# XbeeFeatherWing.net
KiCad netlist of a schematic drawn in EAGLE
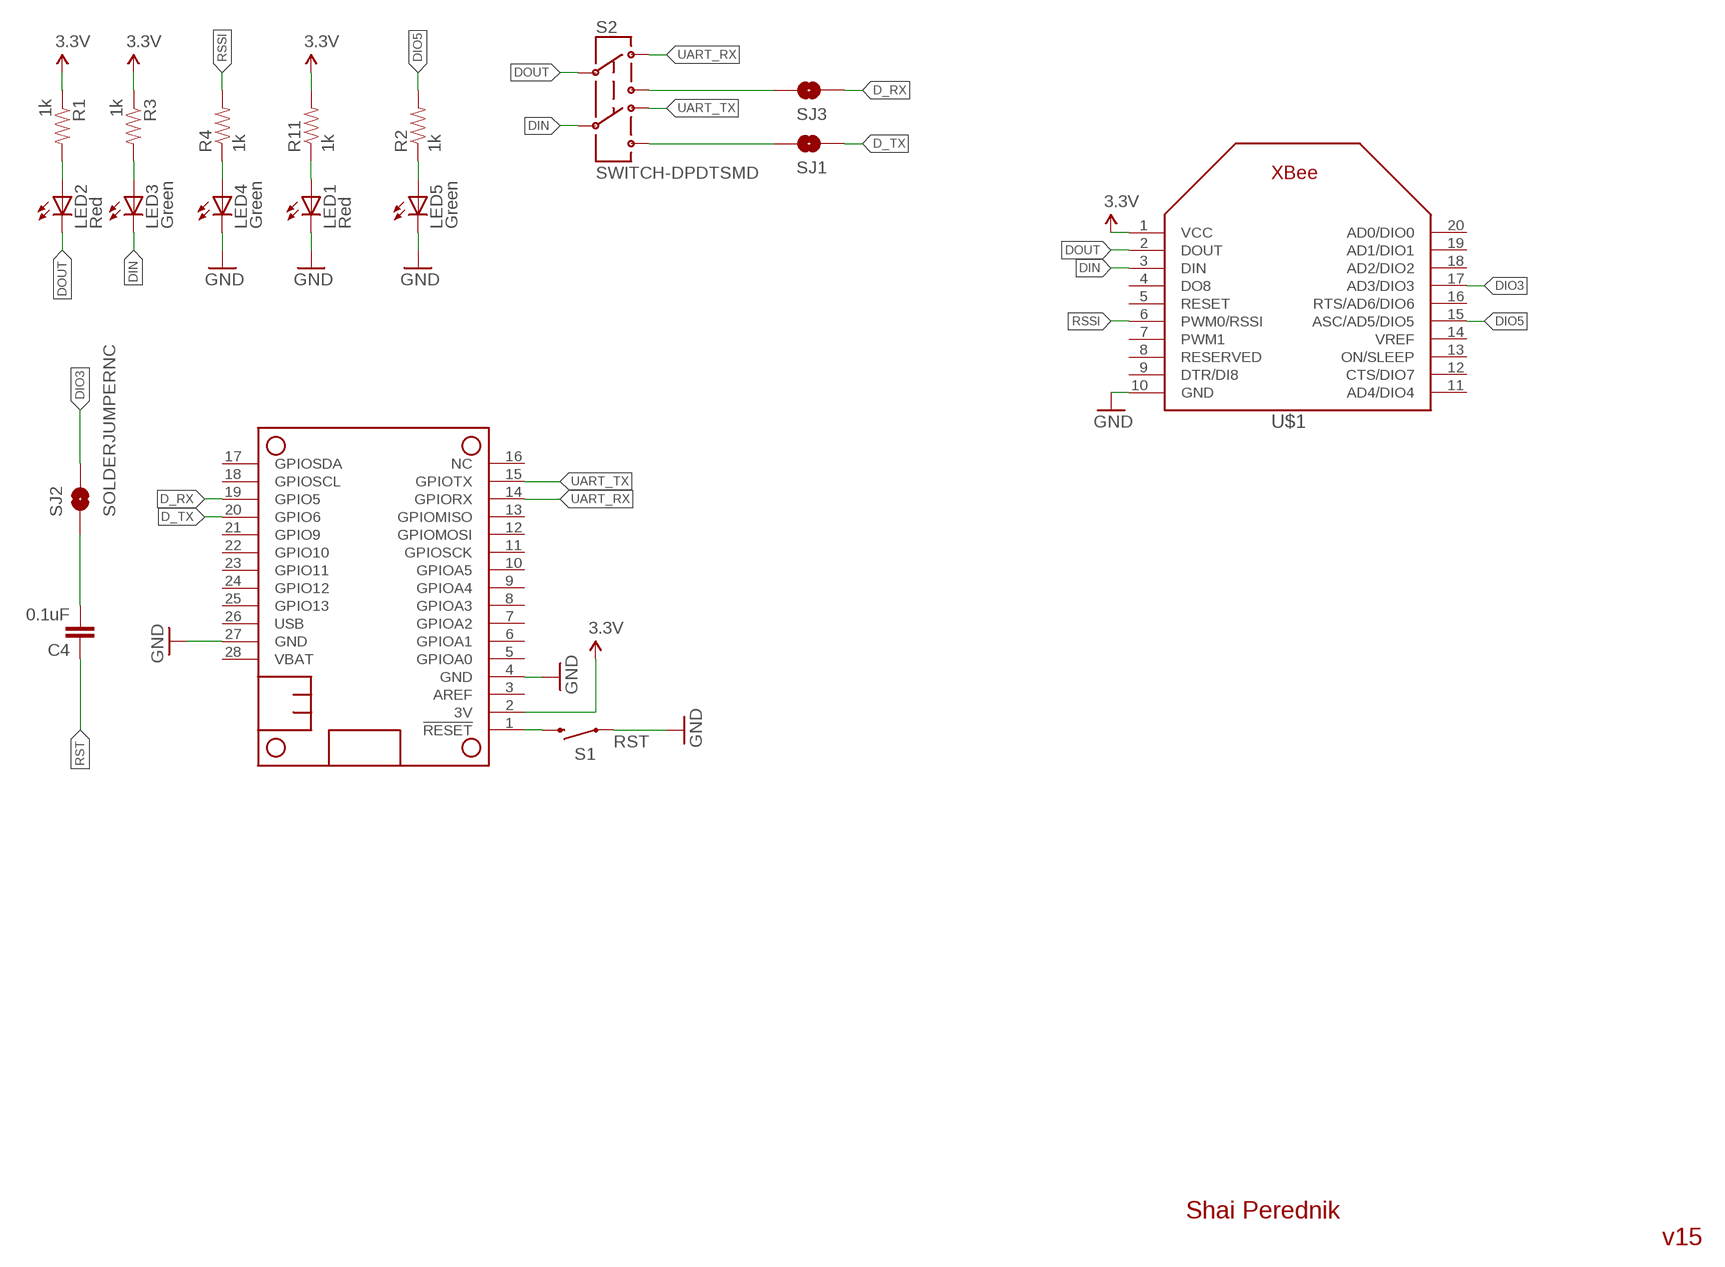
[diagram p0: schematic, sheet 1]

(export (version "E")
  (design (tool "Eeschema 10.0.6"))
  (components
    (comp (ref "C4")
      (value "0.1uF")
      (footprint "eagle-import:0603-CAP")
      (libsource (lib "eagle-import") (part "0.1UF-25V(+80/-20%)(0603)"))
    )
    (comp (ref "LED1")
      (value "Red")
      (footprint "eagle-import:LED-0603")
      (libsource (lib "eagle-import") (part "LED-RED0603"))
    )
    (comp (ref "LED2")
      (value "Red")
      (footprint "eagle-import:LED-0603")
      (libsource (lib "eagle-import") (part "LED-RED0603"))
    )
    (comp (ref "LED3")
      (value "Green")
      (footprint "eagle-import:LED-0603")
      (libsource (lib "eagle-import") (part "LED-GREEN0603"))
    )
    (comp (ref "LED4")
      (value "Green")
      (footprint "eagle-import:LED-0603")
      (libsource (lib "eagle-import") (part "LED-GREEN0603"))
    )
    (comp (ref "LED5")
      (value "Green")
      (footprint "eagle-import:LED-0603")
      (libsource (lib "eagle-import") (part "LED-GREEN0603"))
    )
    (comp (ref "MS2")
      (value "MICROSHIELD_NODIM")
      (footprint "eagle-import:MICROSHIELD_DIM")
      (libsource (lib "eagle-import") (part "MICROSHIELD_NODIM"))
    )
    (comp (ref "R1")
      (value "1k")
      (footprint "eagle-import:0603-RES")
      (libsource (lib "eagle-import") (part "1KOHM1/10W1%(0603)"))
    )
    (comp (ref "R2")
      (value "1k")
      (footprint "eagle-import:0603-RES")
      (libsource (lib "eagle-import") (part "1KOHM1/10W1%(0603)"))
    )
    (comp (ref "R3")
      (value "1k")
      (footprint "eagle-import:0603-RES")
      (libsource (lib "eagle-import") (part "1KOHM1/10W1%(0603)"))
    )
    (comp (ref "R4")
      (value "1k")
      (footprint "eagle-import:0603-RES")
      (libsource (lib "eagle-import") (part "1KOHM1/10W1%(0603)"))
    )
    (comp (ref "R11")
      (value "1k")
      (footprint "eagle-import:0603-RES")
      (libsource (lib "eagle-import") (part "1KOHM1/10W1%(0603)"))
    )
    (comp (ref "S1")
      (value "SWITCH-MOMENTARY-2SMD")
      (footprint "eagle-import:TACTILE_SWITCH_SMD")
      (libsource (lib "eagle-import") (part "SWITCH-MOMENTARY-2SMD"))
    )
    (comp (ref "S2")
      (value "SWITCH-DPDTSMD")
      (footprint "eagle-import:AYZ0202")
      (libsource (lib "eagle-import") (part "SWITCH-DPDTSMD"))
    )
    (comp (ref "SJ1")
      (value "D_TX")
      (footprint "eagle-import:SJ_2S")
      (libsource (lib "eagle-import") (part "SOLDERJUMPERNC"))
    )
    (comp (ref "SJ2")
      (value "SOLDERJUMPERNC")
      (footprint "eagle-import:SJ_2S")
      (libsource (lib "eagle-import") (part "SparkFun-Retired_SOLDERJUMPERNC"))
    )
    (comp (ref "SJ3")
      (value "D_RX")
      (footprint "eagle-import:SJ_2S")
      (libsource (lib "eagle-import") (part "SOLDERJUMPERNC"))
    )
    (comp (ref "U$1")
      (value "XBEE")
      (footprint "eagle-import:XBEE")
      (libsource (lib "eagle-import") (part "XBEE"))
    )
  )
  (nets
    (net (code "1") (name "/USB") (class "Default")
      (node (ref "MS2") (pin "26") (pinfunction "USB_26") (pintype "power_in"))
    )
    (net (code "2") (name "/VBAT") (class "Default")
      (node (ref "MS2") (pin "28") (pinfunction "VBAT_28") (pintype "power_in"))
    )
    (net (code "3") (name "3.3V") (class "Default")
      (node (ref "MS2") (pin "2") (pinfunction "3V_2") (pintype "power_in"))
      (node (ref "R1") (pin "1") (pinfunction "1_1") (pintype "passive"))
      (node (ref "R11") (pin "2") (pinfunction "2_2") (pintype "passive"))
      (node (ref "R3") (pin "1") (pinfunction "1_1") (pintype "passive"))
      (node (ref "U$1") (pin "1") (pinfunction "VCC_1") (pintype "power_in"))
    )
    (net (code "4") (name "DIN") (class "Default")
      (node (ref "LED3") (pin "C") (pinfunction "C_C") (pintype "passive"))
      (node (ref "S2") (pin "5") (pinfunction "5_5") (pintype "bidirectional"))
      (node (ref "U$1") (pin "3") (pinfunction "DIN_3") (pintype "input"))
    )
    (net (code "5") (name "DIO3") (class "Default")
      (node (ref "SJ2") (pin "2") (pinfunction "2_2") (pintype "passive"))
      (node (ref "U$1") (pin "17") (pinfunction "AD3/DIO3_17") (pintype "bidirectional"))
    )
    (net (code "6") (name "DIO5") (class "Default")
      (node (ref "R2") (pin "2") (pinfunction "2_2") (pintype "passive"))
      (node (ref "U$1") (pin "15") (pinfunction "ASC/AD5/DIO5_15") (pintype "bidirectional"))
    )
    (net (code "7") (name "DOUT") (class "Default")
      (node (ref "LED2") (pin "C") (pinfunction "C_C") (pintype "passive"))
      (node (ref "S2") (pin "2") (pinfunction "2_2") (pintype "bidirectional"))
      (node (ref "U$1") (pin "2") (pinfunction "DOUT_2") (pintype "output"))
    )
    (net (code "8") (name "D_RX") (class "Default")
      (node (ref "MS2") (pin "19") (pinfunction "GPIO5_19") (pintype "bidirectional"))
      (node (ref "SJ3") (pin "1") (pinfunction "1_1") (pintype "passive"))
    )
    (net (code "9") (name "D_TX") (class "Default")
      (node (ref "MS2") (pin "20") (pinfunction "GPIO6_20") (pintype "bidirectional"))
      (node (ref "SJ1") (pin "1") (pinfunction "1_1") (pintype "passive"))
    )
    (net (code "10") (name "GND") (class "Default")
      (node (ref "LED1") (pin "C") (pinfunction "C_C") (pintype "passive"))
      (node (ref "LED4") (pin "C") (pinfunction "C_C") (pintype "passive"))
      (node (ref "LED5") (pin "C") (pinfunction "C_C") (pintype "passive"))
      (node (ref "MS2") (pin "27") (pinfunction "GND_27") (pintype "power_in"))
      (node (ref "MS2") (pin "4") (pinfunction "GND_4") (pintype "power_in"))
      (node (ref "S1") (pin "1") (pinfunction "1_1") (pintype "passive"))
      (node (ref "U$1") (pin "10") (pinfunction "GND_10") (pintype "power_in"))
    )
    (net (code "11") (name "Net-(C4-Pad2)") (class "Default")
      (node (ref "C4") (pin "2") (pinfunction "2_2") (pintype "passive"))
      (node (ref "SJ2") (pin "1") (pinfunction "1_1") (pintype "passive"))
    )
    (net (code "12") (name "Net-(LED1-PadA)") (class "Default")
      (node (ref "LED1") (pin "A") (pinfunction "A_A") (pintype "passive"))
      (node (ref "R11") (pin "1") (pinfunction "1_1") (pintype "passive"))
    )
    (net (code "13") (name "Net-(LED2-PadA)") (class "Default")
      (node (ref "LED2") (pin "A") (pinfunction "A_A") (pintype "passive"))
      (node (ref "R1") (pin "2") (pinfunction "2_2") (pintype "passive"))
    )
    (net (code "14") (name "Net-(LED3-PadA)") (class "Default")
      (node (ref "LED3") (pin "A") (pinfunction "A_A") (pintype "passive"))
      (node (ref "R3") (pin "2") (pinfunction "2_2") (pintype "passive"))
    )
    (net (code "15") (name "Net-(LED4-PadA)") (class "Default")
      (node (ref "LED4") (pin "A") (pinfunction "A_A") (pintype "passive"))
      (node (ref "R4") (pin "1") (pinfunction "1_1") (pintype "passive"))
    )
    (net (code "16") (name "Net-(LED5-PadA)") (class "Default")
      (node (ref "LED5") (pin "A") (pinfunction "A_A") (pintype "passive"))
      (node (ref "R2") (pin "1") (pinfunction "1_1") (pintype "passive"))
    )
    (net (code "17") (name "Net-(S2-Pad3)") (class "Default")
      (node (ref "S2") (pin "3") (pinfunction "3_3") (pintype "bidirectional"))
      (node (ref "SJ3") (pin "2") (pinfunction "2_2") (pintype "passive"))
    )
    (net (code "18") (name "Net-(S2-Pad6)") (class "Default")
      (node (ref "S2") (pin "6") (pinfunction "6_6") (pintype "bidirectional"))
      (node (ref "SJ1") (pin "2") (pinfunction "2_2") (pintype "passive"))
    )
    (net (code "19") (name "RSSI") (class "Default")
      (node (ref "R4") (pin "2") (pinfunction "2_2") (pintype "passive"))
      (node (ref "U$1") (pin "6") (pinfunction "PWM0/RSSI_6") (pintype "output"))
    )
    (net (code "20") (name "RST") (class "Default")
      (node (ref "C4") (pin "1") (pinfunction "1_1") (pintype "passive"))
      (node (ref "MS2") (pin "1") (pinfunction "~{RESET}_1") (pintype "input"))
      (node (ref "S1") (pin "3") (pinfunction "2_3") (pintype "passive"))
    )
    (net (code "21") (name "UART_RX") (class "Default")
      (node (ref "MS2") (pin "14") (pinfunction "GPIORX_14") (pintype "bidirectional"))
      (node (ref "S2") (pin "1") (pinfunction "1_1") (pintype "bidirectional"))
    )
    (net (code "22") (name "UART_TX") (class "Default")
      (node (ref "MS2") (pin "15") (pinfunction "GPIOTX_15") (pintype "bidirectional"))
      (node (ref "S2") (pin "4") (pinfunction "4_4") (pintype "bidirectional"))
    )
    (net (code "23") (name "unconnected-(MS2-AREF-Pad3)") (class "Default")
      (node (ref "MS2") (pin "3") (pinfunction "AREF_3") (pintype "passive"))
    )
    (net (code "24") (name "unconnected-(MS2-GPIO9-Pad21)") (class "Default")
      (node (ref "MS2") (pin "21") (pinfunction "GPIO9_21") (pintype "bidirectional"))
    )
    (net (code "25") (name "unconnected-(MS2-GPIO10-Pad22)") (class "Default")
      (node (ref "MS2") (pin "22") (pinfunction "GPIO10_22") (pintype "bidirectional"))
    )
    (net (code "26") (name "unconnected-(MS2-GPIO11-Pad23)") (class "Default")
      (node (ref "MS2") (pin "23") (pinfunction "GPIO11_23") (pintype "bidirectional"))
    )
    (net (code "27") (name "unconnected-(MS2-GPIO12-Pad24)") (class "Default")
      (node (ref "MS2") (pin "24") (pinfunction "GPIO12_24") (pintype "bidirectional"))
    )
    (net (code "28") (name "unconnected-(MS2-GPIO13-Pad25)") (class "Default")
      (node (ref "MS2") (pin "25") (pinfunction "GPIO13_25") (pintype "bidirectional"))
    )
    (net (code "29") (name "unconnected-(MS2-GPIOA0-Pad5)") (class "Default")
      (node (ref "MS2") (pin "5") (pinfunction "GPIOA0_5") (pintype "bidirectional"))
    )
    (net (code "30") (name "unconnected-(MS2-GPIOA1-Pad6)") (class "Default")
      (node (ref "MS2") (pin "6") (pinfunction "GPIOA1_6") (pintype "bidirectional"))
    )
    (net (code "31") (name "unconnected-(MS2-GPIOA2-Pad7)") (class "Default")
      (node (ref "MS2") (pin "7") (pinfunction "GPIOA2_7") (pintype "bidirectional"))
    )
    (net (code "32") (name "unconnected-(MS2-GPIOA3-Pad8)") (class "Default")
      (node (ref "MS2") (pin "8") (pinfunction "GPIOA3_8") (pintype "bidirectional"))
    )
    (net (code "33") (name "unconnected-(MS2-GPIOA4-Pad9)") (class "Default")
      (node (ref "MS2") (pin "9") (pinfunction "GPIOA4_9") (pintype "bidirectional"))
    )
    (net (code "34") (name "unconnected-(MS2-GPIOA5-Pad10)") (class "Default")
      (node (ref "MS2") (pin "10") (pinfunction "GPIOA5_10") (pintype "bidirectional"))
    )
    (net (code "35") (name "unconnected-(MS2-GPIOMISO-Pad13)") (class "Default")
      (node (ref "MS2") (pin "13") (pinfunction "GPIOMISO_13") (pintype "bidirectional"))
    )
    (net (code "36") (name "unconnected-(MS2-GPIOMOSI-Pad12)") (class "Default")
      (node (ref "MS2") (pin "12") (pinfunction "GPIOMOSI_12") (pintype "bidirectional"))
    )
    (net (code "37") (name "unconnected-(MS2-GPIOSCK-Pad11)") (class "Default")
      (node (ref "MS2") (pin "11") (pinfunction "GPIOSCK_11") (pintype "bidirectional"))
    )
    (net (code "38") (name "unconnected-(MS2-GPIOSCL-Pad18)") (class "Default")
      (node (ref "MS2") (pin "18") (pinfunction "GPIOSCL_18") (pintype "bidirectional"))
    )
    (net (code "39") (name "unconnected-(MS2-GPIOSDA-Pad17)") (class "Default")
      (node (ref "MS2") (pin "17") (pinfunction "GPIOSDA_17") (pintype "bidirectional"))
    )
    (net (code "40") (name "unconnected-(MS2-NC-Pad16)") (class "Default")
      (node (ref "MS2") (pin "16") (pinfunction "NC_16") (pintype "passive"))
    )
    (net (code "41") (name "unconnected-(U$1-AD0{slash}DIO0-Pad20)") (class "Default")
      (node (ref "U$1") (pin "20") (pinfunction "AD0/DIO0_20") (pintype "bidirectional"))
    )
    (net (code "42") (name "unconnected-(U$1-AD1{slash}DIO1-Pad19)") (class "Default")
      (node (ref "U$1") (pin "19") (pinfunction "AD1/DIO1_19") (pintype "bidirectional"))
    )
    (net (code "43") (name "unconnected-(U$1-AD2{slash}DIO2-Pad18)") (class "Default")
      (node (ref "U$1") (pin "18") (pinfunction "AD2/DIO2_18") (pintype "bidirectional"))
    )
    (net (code "44") (name "unconnected-(U$1-AD4{slash}DIO4-Pad11)") (class "Default")
      (node (ref "U$1") (pin "11") (pinfunction "AD4/DIO4_11") (pintype "bidirectional"))
    )
    (net (code "45") (name "unconnected-(U$1-CTS{slash}DIO7-Pad12)") (class "Default")
      (node (ref "U$1") (pin "12") (pinfunction "CTS/DIO7_12") (pintype "bidirectional"))
    )
    (net (code "46") (name "unconnected-(U$1-DO8-Pad4)") (class "Default")
      (node (ref "U$1") (pin "4") (pinfunction "DO8_4") (pintype "output"))
    )
    (net (code "47") (name "unconnected-(U$1-DTR{slash}DI8-Pad9)") (class "Default")
      (node (ref "U$1") (pin "9") (pinfunction "DTR/DI8_9") (pintype "input"))
    )
    (net (code "48") (name "unconnected-(U$1-ON{slash}SLEEP-Pad13)") (class "Default")
      (node (ref "U$1") (pin "13") (pinfunction "ON/SLEEP_13") (pintype "output"))
    )
    (net (code "49") (name "unconnected-(U$1-PWM1-Pad7)") (class "Default")
      (node (ref "U$1") (pin "7") (pinfunction "PWM1_7") (pintype "output"))
    )
    (net (code "50") (name "unconnected-(U$1-RESERVED-Pad8)") (class "Default")
      (node (ref "U$1") (pin "8") (pinfunction "RESERVED_8") (pintype "no_connect"))
    )
    (net (code "51") (name "unconnected-(U$1-RESET-Pad5)") (class "Default")
      (node (ref "U$1") (pin "5") (pinfunction "RESET_5") (pintype "input"))
    )
    (net (code "52") (name "unconnected-(U$1-RTS{slash}AD6{slash}DIO6-Pad16)") (class "Default")
      (node (ref "U$1") (pin "16") (pinfunction "RTS/AD6/DIO6_16") (pintype "bidirectional"))
    )
    (net (code "53") (name "unconnected-(U$1-VREF-Pad14)") (class "Default")
      (node (ref "U$1") (pin "14") (pinfunction "VREF_14") (pintype "input"))
    )
  )
)
